# pinheader_pigoda.net
KiCad netlist of a schematic drawn in EAGLE
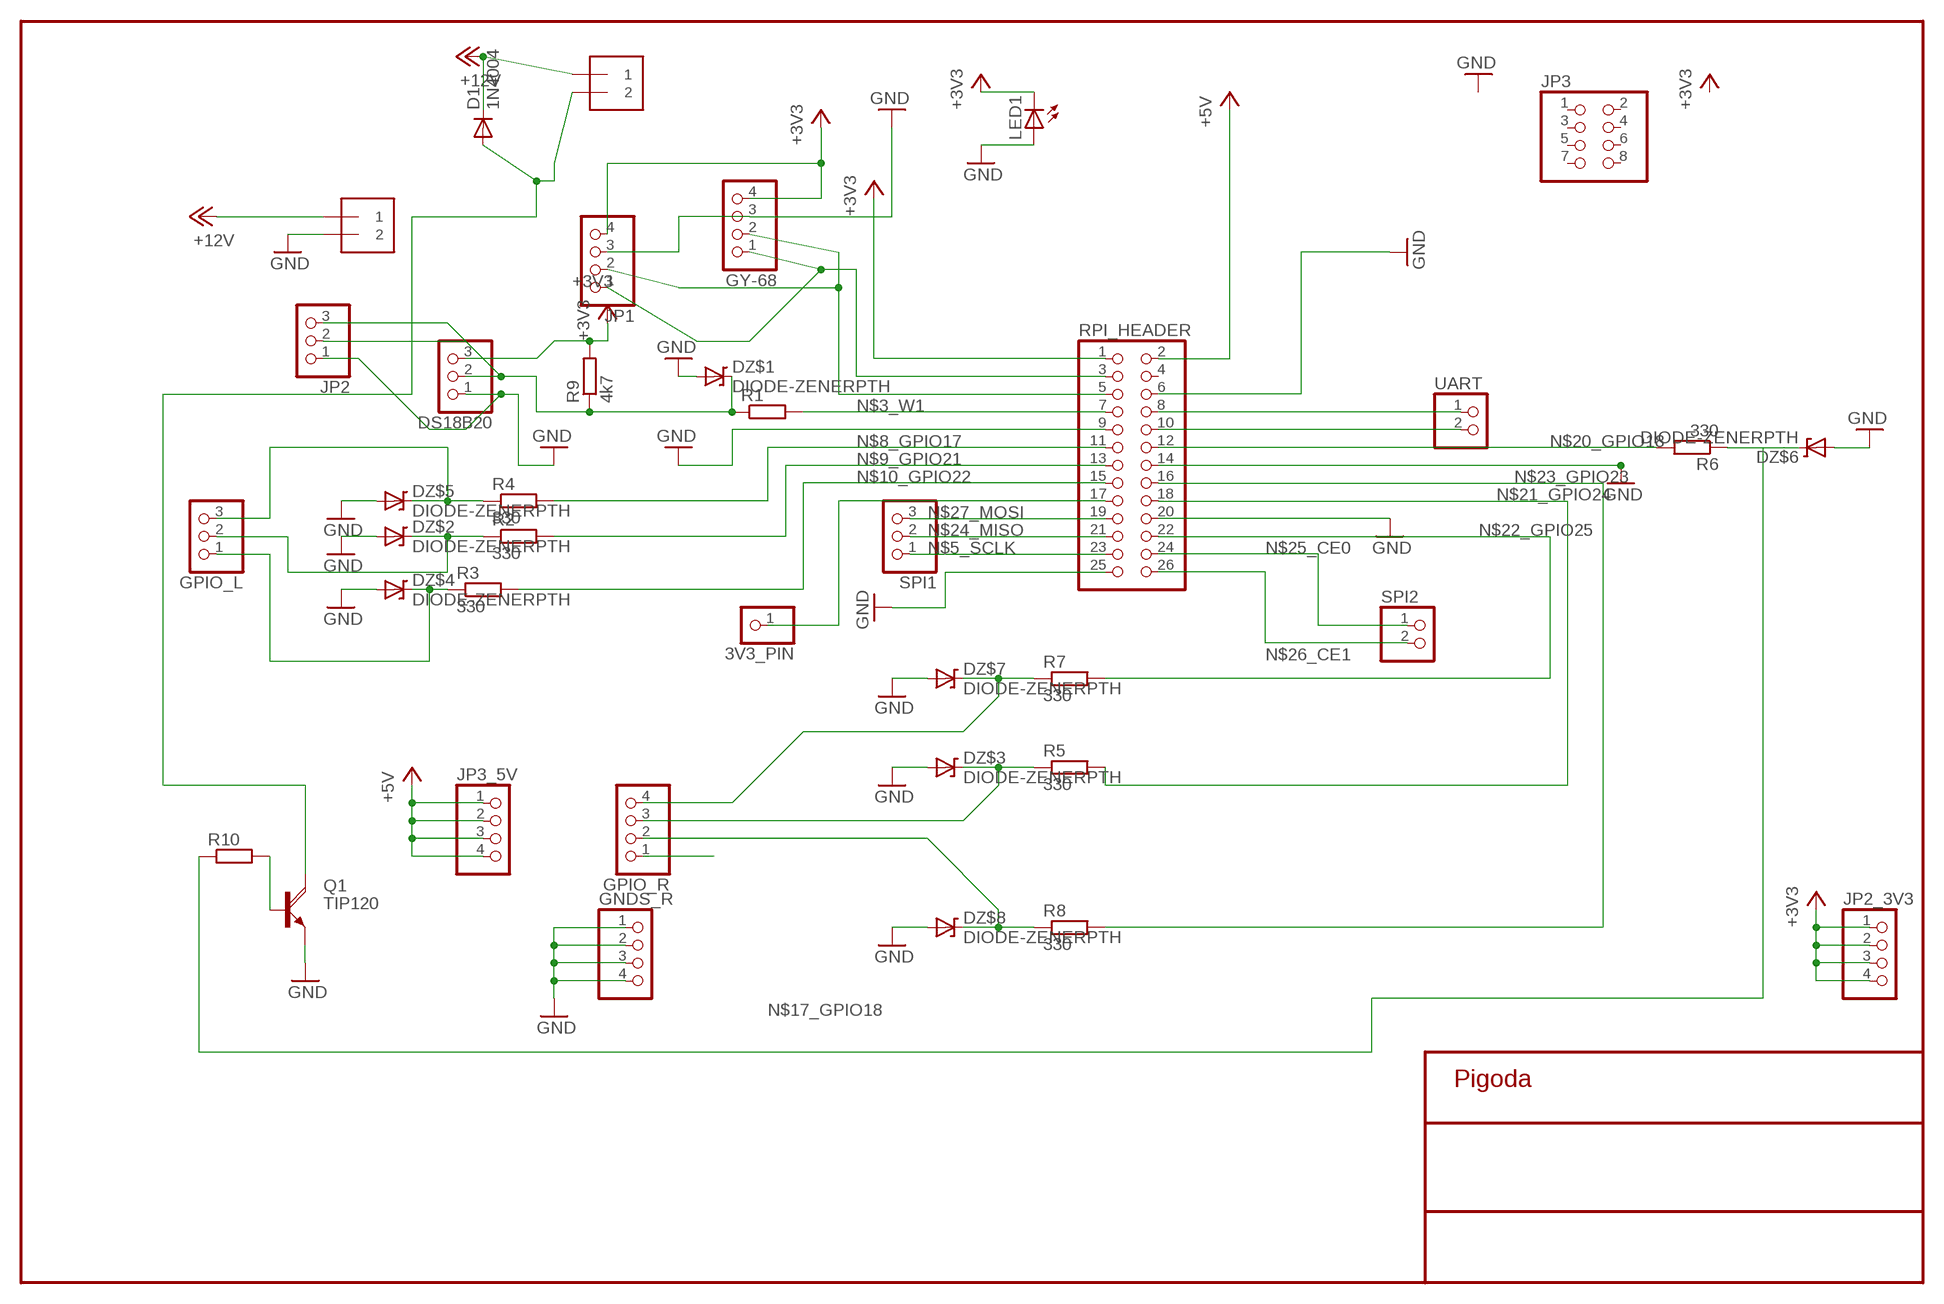
[diagram p0: schematic, sheet 1]

(export (version "E")
  (design (tool "Eeschema 10.0.6"))
  (components
    (comp (ref "3V3_PIN")
      (value "PINHD-1X1")
      (footprint "eagle-import:1X01")
      (libsource (lib "eagle-import") (part "PINHD-1X1"))
    )
    (comp (ref "12V_IN")
      (value "1X2-3.5MM")
      (footprint "eagle-import:1X2-3.5MM")
      (libsource (lib "eagle-import") (part "1X2-3.5MM"))
    )
    (comp (ref "12V_IOUT")
      (value "1X2-3.5MM")
      (footprint "eagle-import:1X2-3.5MM")
      (libsource (lib "eagle-import") (part "1X2-3.5MM"))
    )
    (comp (ref "D1")
      (value "1N4004")
      (footprint "eagle-import:DO41-10")
      (libsource (lib "eagle-import") (part "1N4004"))
    )
    (comp (ref "DS18B20")
      (value "PINHD-1X3")
      (footprint "eagle-import:1X03")
      (libsource (lib "eagle-import") (part "PINHD-1X3"))
    )
    (comp (ref "DZ$1")
      (value "DIODE-ZENERPTH")
      (footprint "eagle-import:DIODE-ZENER")
      (libsource (lib "eagle-import") (part "DIODE-ZENERPTH"))
    )
    (comp (ref "DZ$2")
      (value "DIODE-ZENERPTH")
      (footprint "eagle-import:DIODE-ZENER")
      (libsource (lib "eagle-import") (part "DIODE-ZENERPTH"))
    )
    (comp (ref "DZ$3")
      (value "DIODE-ZENERPTH")
      (footprint "eagle-import:DIODE-ZENER")
      (libsource (lib "eagle-import") (part "DIODE-ZENERPTH"))
    )
    (comp (ref "DZ$4")
      (value "DIODE-ZENERPTH")
      (footprint "eagle-import:DIODE-ZENER")
      (libsource (lib "eagle-import") (part "DIODE-ZENERPTH"))
    )
    (comp (ref "DZ$5")
      (value "DIODE-ZENERPTH")
      (footprint "eagle-import:DIODE-ZENER")
      (libsource (lib "eagle-import") (part "DIODE-ZENERPTH"))
    )
    (comp (ref "DZ$6")
      (value "DIODE-ZENERPTH")
      (footprint "eagle-import:DIODE-ZENER")
      (libsource (lib "eagle-import") (part "DIODE-ZENERPTH"))
    )
    (comp (ref "DZ$7")
      (value "DIODE-ZENERPTH")
      (footprint "eagle-import:DIODE-ZENER")
      (libsource (lib "eagle-import") (part "DIODE-ZENERPTH"))
    )
    (comp (ref "DZ$8")
      (value "DIODE-ZENERPTH")
      (footprint "eagle-import:DIODE-ZENER")
      (libsource (lib "eagle-import") (part "DIODE-ZENERPTH"))
    )
    (comp (ref "GNDS_R")
      (value "PINHD-1X4")
      (footprint "eagle-import:1X04")
      (libsource (lib "eagle-import") (part "PINHD-1X4"))
    )
    (comp (ref "GPIO_L")
      (value "PINHD-1X3")
      (footprint "eagle-import:1X03")
      (libsource (lib "eagle-import") (part "PINHD-1X3"))
    )
    (comp (ref "GPIO_R")
      (value "PINHD-1X4")
      (footprint "eagle-import:1X04")
      (libsource (lib "eagle-import") (part "PINHD-1X4"))
    )
    (comp (ref "GY-68")
      (value "PINHD-1X4")
      (footprint "eagle-import:1X04")
      (libsource (lib "eagle-import") (part "PINHD-1X4"))
    )
    (comp (ref "JP1")
      (value "PINHD-1X4")
      (footprint "eagle-import:1X04")
      (libsource (lib "eagle-import") (part "PINHD-1X4"))
    )
    (comp (ref "JP2")
      (value "PINHD-1X3")
      (footprint "eagle-import:1X03")
      (libsource (lib "eagle-import") (part "PINHD-1X3"))
    )
    (comp (ref "JP2_3V3")
      (value "PINHD-1X4")
      (footprint "eagle-import:1X04")
      (libsource (lib "eagle-import") (part "PINHD-1X4"))
    )
    (comp (ref "JP3")
      (value "PINHD-2X4/90")
      (footprint "eagle-import:2X04_90")
      (libsource (lib "eagle-import") (part "PINHD-2X4/90"))
    )
    (comp (ref "JP3_5V")
      (value "PINHD-1X4")
      (footprint "eagle-import:1X04")
      (libsource (lib "eagle-import") (part "PINHD-1X4"))
    )
    (comp (ref "LED1")
      (value "LED3MM")
      (footprint "eagle-import:LED3MM")
      (libsource (lib "eagle-import") (part "LED3MM"))
    )
    (comp (ref "Q1")
      (value "TIP120")
      (footprint "eagle-import:TO220AH")
      (libsource (lib "eagle-import") (part "TIP120"))
    )
    (comp (ref "R1")
      (value "R-EU_0204/7")
      (footprint "eagle-import:0204_7")
      (libsource (lib "eagle-import") (part "R-EU_0204/7"))
    )
    (comp (ref "R2")
      (value "330")
      (footprint "eagle-import:0204_7")
      (libsource (lib "eagle-import") (part "R-EU_0204/7"))
    )
    (comp (ref "R3")
      (value "330")
      (footprint "eagle-import:0204_7")
      (libsource (lib "eagle-import") (part "R-EU_0204/7"))
    )
    (comp (ref "R4")
      (value "330")
      (footprint "eagle-import:0204_7")
      (libsource (lib "eagle-import") (part "R-EU_0204/7"))
    )
    (comp (ref "R5")
      (value "330")
      (footprint "eagle-import:0204_7")
      (libsource (lib "eagle-import") (part "R-EU_0204/7"))
    )
    (comp (ref "R6")
      (value "330")
      (footprint "eagle-import:0204_7")
      (libsource (lib "eagle-import") (part "R-EU_0204/7"))
    )
    (comp (ref "R7")
      (value "330")
      (footprint "eagle-import:0204_7")
      (libsource (lib "eagle-import") (part "R-EU_0204/7"))
    )
    (comp (ref "R8")
      (value "330")
      (footprint "eagle-import:0204_7")
      (libsource (lib "eagle-import") (part "R-EU_0204/7"))
    )
    (comp (ref "R9")
      (value "4k7")
      (footprint "eagle-import:0204_5")
      (libsource (lib "eagle-import") (part "R-EU_0204/5"))
    )
    (comp (ref "R10")
      (value "R-EU_0204/5")
      (footprint "eagle-import:0204_5")
      (libsource (lib "eagle-import") (part "R-EU_0204/5"))
    )
    (comp (ref "RPI_HEADER")
      (value "PINHD-2X13")
      (footprint "eagle-import:2X13")
      (libsource (lib "eagle-import") (part "PINHD-2X13"))
    )
    (comp (ref "SPI1")
      (value "PINHD-1X3")
      (footprint "eagle-import:1X03")
      (libsource (lib "eagle-import") (part "PINHD-1X3"))
    )
    (comp (ref "SPI2")
      (value "PINHD-1X2")
      (footprint "eagle-import:1X02")
      (libsource (lib "eagle-import") (part "PINHD-1X2"))
    )
    (comp (ref "UART")
      (value "PINHD-1X2")
      (footprint "eagle-import:1X02")
      (libsource (lib "eagle-import") (part "PINHD-1X2"))
    )
  )
  (nets
    (net (code "1") (name "+3V3") (class "Default")
      (node (ref "DS18B20") (pin "3") (pinfunction "3_3") (pintype "passive"))
      (node (ref "GY-68") (pin "4") (pinfunction "4_4") (pintype "passive"))
      (node (ref "JP1") (pin "4") (pinfunction "4_4") (pintype "passive"))
      (node (ref "JP2") (pin "3") (pinfunction "3_3") (pintype "passive"))
      (node (ref "JP2_3V3") (pin "1") (pinfunction "1_1") (pintype "passive"))
      (node (ref "JP2_3V3") (pin "2") (pinfunction "2_2") (pintype "passive"))
      (node (ref "JP2_3V3") (pin "3") (pinfunction "3_3") (pintype "passive"))
      (node (ref "JP2_3V3") (pin "4") (pinfunction "4_4") (pintype "passive"))
      (node (ref "LED1") (pin "K") (pinfunction "C_K") (pintype "passive"))
      (node (ref "R9") (pin "2") (pinfunction "2_2") (pintype "passive"))
      (node (ref "RPI_HEADER") (pin "1") (pinfunction "1_1") (pintype "passive"))
    )
    (net (code "2") (name "+5V") (class "Default")
      (node (ref "JP3_5V") (pin "1") (pinfunction "1_1") (pintype "passive"))
      (node (ref "JP3_5V") (pin "2") (pinfunction "2_2") (pintype "passive"))
      (node (ref "JP3_5V") (pin "3") (pinfunction "3_3") (pintype "passive"))
      (node (ref "JP3_5V") (pin "4") (pinfunction "4_4") (pintype "passive"))
      (node (ref "RPI_HEADER") (pin "2") (pinfunction "2_2") (pintype "passive"))
    )
    (net (code "3") (name "+12V") (class "Default")
      (node (ref "12V_IN") (pin "1") (pinfunction "1_1") (pintype "passive"))
      (node (ref "12V_IOUT") (pin "1") (pinfunction "1_1") (pintype "passive"))
      (node (ref "D1") (pin "C") (pinfunction "C_C") (pintype "passive"))
    )
    (net (code "4") (name "/N$3_W1") (class "Default")
      (node (ref "R1") (pin "2") (pinfunction "2_2") (pintype "passive"))
      (node (ref "RPI_HEADER") (pin "7") (pinfunction "7_7") (pintype "passive"))
    )
    (net (code "5") (name "/N$5_SCLK") (class "Default")
      (node (ref "RPI_HEADER") (pin "23") (pinfunction "23_23") (pintype "passive"))
      (node (ref "SPI1") (pin "1") (pinfunction "1_1") (pintype "passive"))
    )
    (net (code "6") (name "/N$8_GPIO17") (class "Default")
      (node (ref "R4") (pin "2") (pinfunction "2_2") (pintype "passive"))
      (node (ref "RPI_HEADER") (pin "11") (pinfunction "11_11") (pintype "passive"))
    )
    (net (code "7") (name "/N$9_GPIO21") (class "Default")
      (node (ref "R2") (pin "2") (pinfunction "2_2") (pintype "passive"))
      (node (ref "RPI_HEADER") (pin "13") (pinfunction "13_13") (pintype "passive"))
    )
    (net (code "8") (name "/N$10_GPIO22") (class "Default")
      (node (ref "R3") (pin "2") (pinfunction "2_2") (pintype "passive"))
      (node (ref "RPI_HEADER") (pin "15") (pinfunction "15_15") (pintype "passive"))
    )
    (net (code "9") (name "/N$17_GPIO18") (class "Default")
      (node (ref "DZ$6") (pin "P$1") (pinfunction "C_P$1") (pintype "passive"))
      (node (ref "R10") (pin "1") (pinfunction "1_1") (pintype "passive"))
      (node (ref "R6") (pin "1") (pinfunction "1_1") (pintype "passive"))
    )
    (net (code "10") (name "/N$20_GPIO18") (class "Default")
      (node (ref "R6") (pin "2") (pinfunction "2_2") (pintype "passive"))
      (node (ref "RPI_HEADER") (pin "12") (pinfunction "12_12") (pintype "passive"))
    )
    (net (code "11") (name "/N$21_GPIO24") (class "Default")
      (node (ref "R5") (pin "2") (pinfunction "2_2") (pintype "passive"))
      (node (ref "RPI_HEADER") (pin "18") (pinfunction "18_18") (pintype "passive"))
    )
    (net (code "12") (name "/N$22_GPIO25") (class "Default")
      (node (ref "R7") (pin "2") (pinfunction "2_2") (pintype "passive"))
      (node (ref "RPI_HEADER") (pin "22") (pinfunction "22_22") (pintype "passive"))
    )
    (net (code "13") (name "/N$23_GPIO23") (class "Default")
      (node (ref "R8") (pin "2") (pinfunction "2_2") (pintype "passive"))
      (node (ref "RPI_HEADER") (pin "16") (pinfunction "16_16") (pintype "passive"))
    )
    (net (code "14") (name "/N$24_MISO") (class "Default")
      (node (ref "RPI_HEADER") (pin "21") (pinfunction "21_21") (pintype "passive"))
      (node (ref "SPI1") (pin "2") (pinfunction "2_2") (pintype "passive"))
    )
    (net (code "15") (name "/N$25_CE0") (class "Default")
      (node (ref "RPI_HEADER") (pin "24") (pinfunction "24_24") (pintype "passive"))
      (node (ref "SPI2") (pin "1") (pinfunction "1_1") (pintype "passive"))
    )
    (net (code "16") (name "/N$26_CE1") (class "Default")
      (node (ref "RPI_HEADER") (pin "26") (pinfunction "26_26") (pintype "passive"))
      (node (ref "SPI2") (pin "2") (pinfunction "2_2") (pintype "passive"))
    )
    (net (code "17") (name "/N$27_MOSI") (class "Default")
      (node (ref "RPI_HEADER") (pin "19") (pinfunction "19_19") (pintype "passive"))
      (node (ref "SPI1") (pin "3") (pinfunction "3_3") (pintype "passive"))
    )
    (net (code "18") (name "GND") (class "Default")
      (node (ref "12V_IN") (pin "2") (pinfunction "2_2") (pintype "passive"))
      (node (ref "DS18B20") (pin "1") (pinfunction "1_1") (pintype "passive"))
      (node (ref "DZ$1") (pin "P$2") (pinfunction "A_P$2") (pintype "passive"))
      (node (ref "DZ$2") (pin "P$2") (pinfunction "A_P$2") (pintype "passive"))
      (node (ref "DZ$3") (pin "P$2") (pinfunction "A_P$2") (pintype "passive"))
      (node (ref "DZ$4") (pin "P$2") (pinfunction "A_P$2") (pintype "passive"))
      (node (ref "DZ$5") (pin "P$2") (pinfunction "A_P$2") (pintype "passive"))
      (node (ref "DZ$6") (pin "P$2") (pinfunction "A_P$2") (pintype "passive"))
      (node (ref "DZ$7") (pin "P$2") (pinfunction "A_P$2") (pintype "passive"))
      (node (ref "DZ$8") (pin "P$2") (pinfunction "A_P$2") (pintype "passive"))
      (node (ref "GNDS_R") (pin "1") (pinfunction "1_1") (pintype "passive"))
      (node (ref "GNDS_R") (pin "2") (pinfunction "2_2") (pintype "passive"))
      (node (ref "GNDS_R") (pin "3") (pinfunction "3_3") (pintype "passive"))
      (node (ref "GNDS_R") (pin "4") (pinfunction "4_4") (pintype "passive"))
      (node (ref "GY-68") (pin "3") (pinfunction "3_3") (pintype "passive"))
      (node (ref "JP1") (pin "3") (pinfunction "3_3") (pintype "passive"))
      (node (ref "JP2") (pin "1") (pinfunction "1_1") (pintype "passive"))
      (node (ref "LED1") (pin "A") (pinfunction "A_A") (pintype "passive"))
      (node (ref "Q1") (pin "E") (pinfunction "E_E") (pintype "passive"))
      (node (ref "RPI_HEADER") (pin "14") (pinfunction "14_14") (pintype "passive"))
      (node (ref "RPI_HEADER") (pin "20") (pinfunction "20_20") (pintype "passive"))
      (node (ref "RPI_HEADER") (pin "25") (pinfunction "25_25") (pintype "passive"))
      (node (ref "RPI_HEADER") (pin "6") (pinfunction "6_6") (pintype "passive"))
      (node (ref "RPI_HEADER") (pin "9") (pinfunction "9_9") (pintype "passive"))
    )
    (net (code "19") (name "Net-(3V3_PIN-Pad1)") (class "Default")
      (node (ref "3V3_PIN") (pin "1") (pinfunction "1_1") (pintype "passive"))
      (node (ref "RPI_HEADER") (pin "17") (pinfunction "17_17") (pintype "passive"))
    )
    (net (code "20") (name "Net-(12V_IOUT-Pad2)") (class "Default")
      (node (ref "12V_IOUT") (pin "2") (pinfunction "2_2") (pintype "passive"))
      (node (ref "D1") (pin "A") (pinfunction "A_A") (pintype "passive"))
      (node (ref "Q1") (pin "C") (pinfunction "C_C") (pintype "passive"))
    )
    (net (code "21") (name "Net-(DZ$1-C)") (class "Default")
      (node (ref "DS18B20") (pin "2") (pinfunction "2_2") (pintype "passive"))
      (node (ref "DZ$1") (pin "P$1") (pinfunction "C_P$1") (pintype "passive"))
      (node (ref "JP2") (pin "2") (pinfunction "2_2") (pintype "passive"))
      (node (ref "R1") (pin "1") (pinfunction "1_1") (pintype "passive"))
      (node (ref "R9") (pin "1") (pinfunction "1_1") (pintype "passive"))
    )
    (net (code "22") (name "Net-(DZ$2-C)") (class "Default")
      (node (ref "DZ$2") (pin "P$1") (pinfunction "C_P$1") (pintype "passive"))
      (node (ref "GPIO_L") (pin "2") (pinfunction "2_2") (pintype "passive"))
      (node (ref "R2") (pin "1") (pinfunction "1_1") (pintype "passive"))
    )
    (net (code "23") (name "Net-(DZ$3-C)") (class "Default")
      (node (ref "DZ$3") (pin "P$1") (pinfunction "C_P$1") (pintype "passive"))
      (node (ref "GPIO_R") (pin "3") (pinfunction "3_3") (pintype "passive"))
      (node (ref "R5") (pin "1") (pinfunction "1_1") (pintype "passive"))
    )
    (net (code "24") (name "Net-(DZ$4-C)") (class "Default")
      (node (ref "DZ$4") (pin "P$1") (pinfunction "C_P$1") (pintype "passive"))
      (node (ref "GPIO_L") (pin "1") (pinfunction "1_1") (pintype "passive"))
      (node (ref "R3") (pin "1") (pinfunction "1_1") (pintype "passive"))
    )
    (net (code "25") (name "Net-(DZ$5-C)") (class "Default")
      (node (ref "DZ$5") (pin "P$1") (pinfunction "C_P$1") (pintype "passive"))
      (node (ref "GPIO_L") (pin "3") (pinfunction "3_3") (pintype "passive"))
      (node (ref "R4") (pin "1") (pinfunction "1_1") (pintype "passive"))
    )
    (net (code "26") (name "Net-(DZ$7-C)") (class "Default")
      (node (ref "DZ$7") (pin "P$1") (pinfunction "C_P$1") (pintype "passive"))
      (node (ref "GPIO_R") (pin "4") (pinfunction "4_4") (pintype "passive"))
      (node (ref "R7") (pin "1") (pinfunction "1_1") (pintype "passive"))
    )
    (net (code "27") (name "Net-(DZ$8-C)") (class "Default")
      (node (ref "DZ$8") (pin "P$1") (pinfunction "C_P$1") (pintype "passive"))
      (node (ref "GPIO_R") (pin "2") (pinfunction "2_2") (pintype "passive"))
      (node (ref "R8") (pin "1") (pinfunction "1_1") (pintype "passive"))
    )
    (net (code "28") (name "Net-(GY-68-Pad1)") (class "Default")
      (node (ref "GY-68") (pin "1") (pinfunction "1_1") (pintype "passive"))
      (node (ref "JP1") (pin "1") (pinfunction "1_1") (pintype "passive"))
      (node (ref "RPI_HEADER") (pin "3") (pinfunction "3_3") (pintype "passive"))
    )
    (net (code "29") (name "Net-(GY-68-Pad2)") (class "Default")
      (node (ref "GY-68") (pin "2") (pinfunction "2_2") (pintype "passive"))
      (node (ref "JP1") (pin "2") (pinfunction "2_2") (pintype "passive"))
      (node (ref "RPI_HEADER") (pin "5") (pinfunction "5_5") (pintype "passive"))
    )
    (net (code "30") (name "Net-(Q1-PadB)") (class "Default")
      (node (ref "Q1") (pin "B") (pinfunction "B_B") (pintype "passive"))
      (node (ref "R10") (pin "2") (pinfunction "2_2") (pintype "passive"))
    )
    (net (code "31") (name "Net-(RPI_HEADER-Pad8)") (class "Default")
      (node (ref "RPI_HEADER") (pin "8") (pinfunction "8_8") (pintype "passive"))
      (node (ref "UART") (pin "1") (pinfunction "1_1") (pintype "passive"))
    )
    (net (code "32") (name "Net-(RPI_HEADER-Pad10)") (class "Default")
      (node (ref "RPI_HEADER") (pin "10") (pinfunction "10_10") (pintype "passive"))
      (node (ref "UART") (pin "2") (pinfunction "2_2") (pintype "passive"))
    )
    (net (code "33") (name "unconnected-(GPIO_R-Pad1)") (class "Default")
      (node (ref "GPIO_R") (pin "1") (pinfunction "1_1") (pintype "passive"))
    )
    (net (code "34") (name "unconnected-(JP3-Pad1)") (class "Default")
      (node (ref "JP3") (pin "1") (pinfunction "1_1") (pintype "passive"))
    )
    (net (code "35") (name "unconnected-(JP3-Pad2)") (class "Default")
      (node (ref "JP3") (pin "2") (pinfunction "2_2") (pintype "passive"))
    )
    (net (code "36") (name "unconnected-(JP3-Pad3)") (class "Default")
      (node (ref "JP3") (pin "3") (pinfunction "3_3") (pintype "passive"))
    )
    (net (code "37") (name "unconnected-(JP3-Pad4)") (class "Default")
      (node (ref "JP3") (pin "4") (pinfunction "4_4") (pintype "passive"))
    )
    (net (code "38") (name "unconnected-(JP3-Pad5)") (class "Default")
      (node (ref "JP3") (pin "5") (pinfunction "5_5") (pintype "passive"))
    )
    (net (code "39") (name "unconnected-(JP3-Pad6)") (class "Default")
      (node (ref "JP3") (pin "6") (pinfunction "6_6") (pintype "passive"))
    )
    (net (code "40") (name "unconnected-(JP3-Pad7)") (class "Default")
      (node (ref "JP3") (pin "7") (pinfunction "7_7") (pintype "passive"))
    )
    (net (code "41") (name "unconnected-(JP3-Pad8)") (class "Default")
      (node (ref "JP3") (pin "8") (pinfunction "8_8") (pintype "passive"))
    )
    (net (code "42") (name "unconnected-(RPI_HEADER-Pad4)") (class "Default")
      (node (ref "RPI_HEADER") (pin "4") (pinfunction "4_4") (pintype "passive"))
    )
  )
)
